# Thermistor.net
KiCad netlist of a schematic drawn in Altium Designer
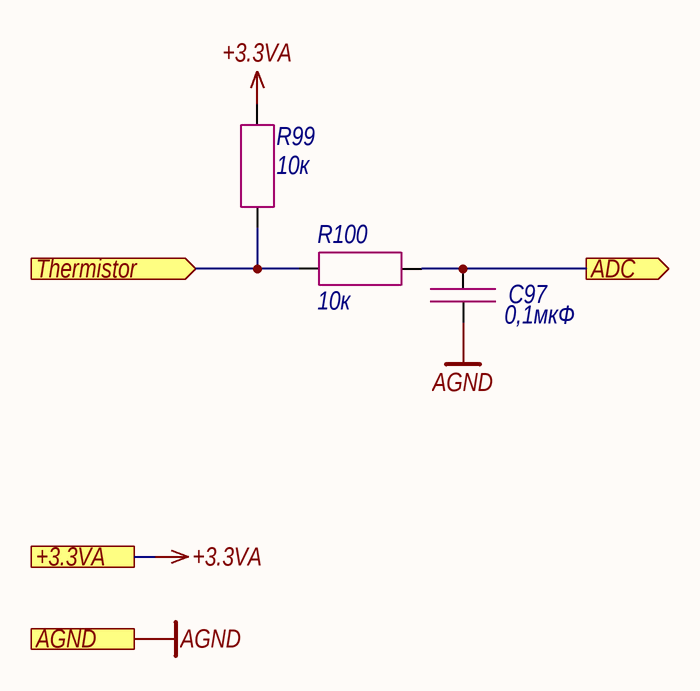
[diagram p0: Thermistor.SchDoc]

(export (version "E")
  (design (tool "Eeschema 10.0.6"))
  (components
    (comp (ref "C97")
      (value "0,1мкФ")
      (footprint "Pcb_library:CAP_0603")
      (fields (field (name "MANUFACTURER") "Murata"))
      (libsource (lib "Schem_library") (part "Capacitor"))
    )
    (comp (ref "R99")
      (value "10к")
      (footprint "Pcb_library:RES_0603")
      (fields (field (name "MANUFACTURER") "Yageo"))
      (libsource (lib "Schem_library") (part "Resistor"))
    )
    (comp (ref "R100")
      (value "10к")
      (footprint "Pcb_library:RES_0603")
      (fields (field (name "MANUFACTURER") "Yageo"))
      (libsource (lib "Schem_library") (part "Resistor"))
    )
  )
  (nets
    (net (code "1") (name "+3.3VA") (class "Default")
      (node (ref "R99") (pin "1") (pinfunction "1_1") (pintype "passive"))
    )
    (net (code "2") (name "/ADC") (class "Default")
      (node (ref "C97") (pin "1") (pinfunction "1_1") (pintype "passive"))
      (node (ref "R100") (pin "2") (pinfunction "2_2") (pintype "passive"))
    )
    (net (code "3") (name "/Thermistor") (class "Default")
      (node (ref "R100") (pin "1") (pinfunction "1_1") (pintype "passive"))
      (node (ref "R99") (pin "2") (pinfunction "2_2") (pintype "passive"))
    )
    (net (code "4") (name "AGND") (class "Default")
      (node (ref "C97") (pin "2") (pinfunction "2_2") (pintype "passive"))
    )
  )
)
